# GPIO.net
KiCad netlist of a schematic drawn in Altium Designer
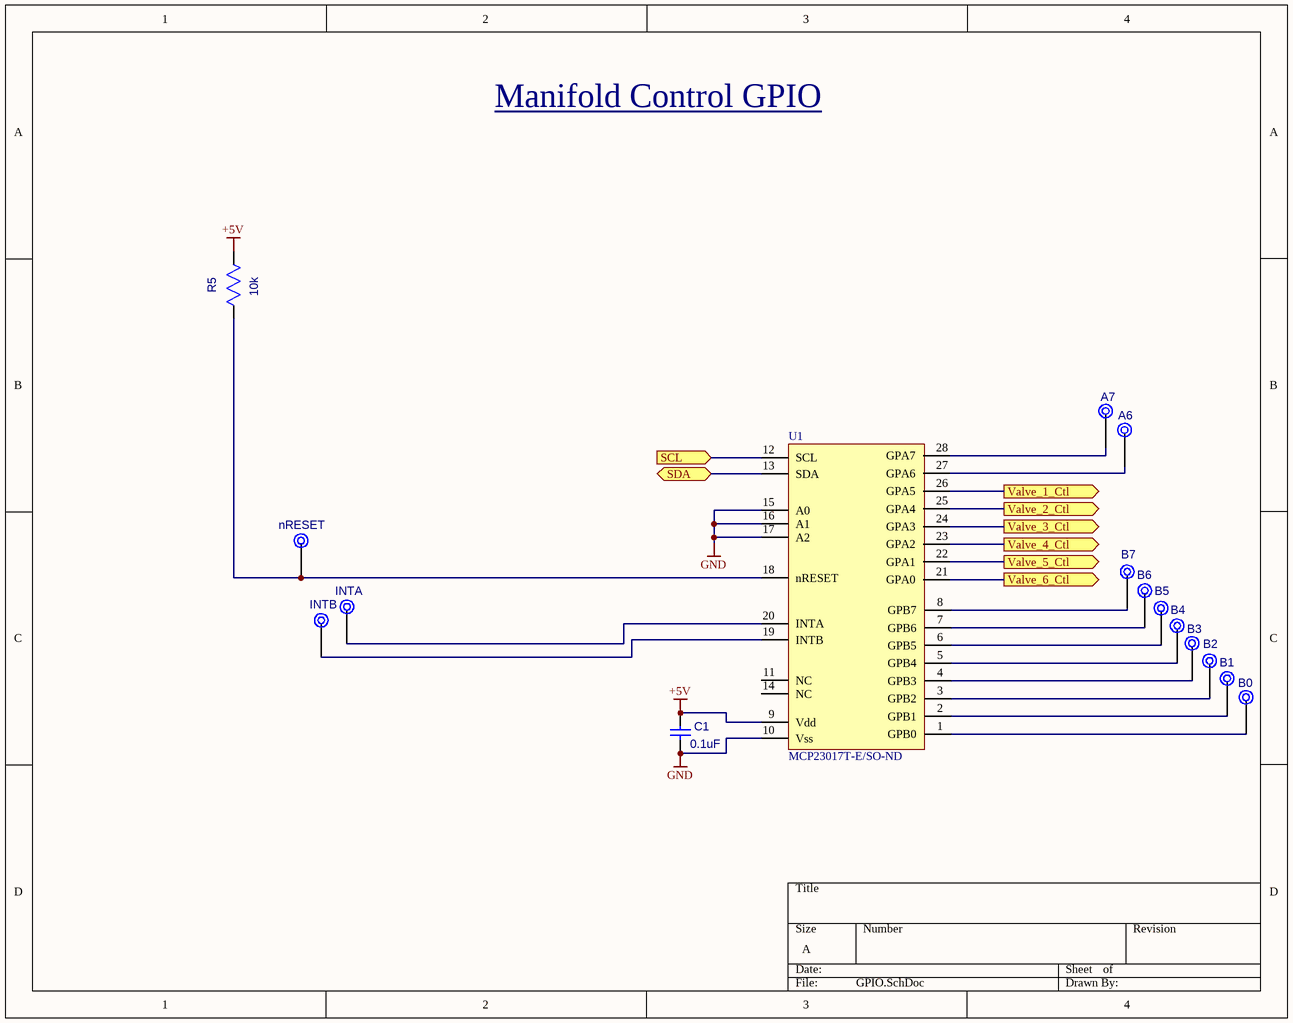
[diagram p0: GPIO.SchDoc]

(export (version "E")
  (design (tool "Eeschema 10.0.6"))
  (components
    (comp (ref "C1")
      (value "0.1uF")
      (footprint "CC1206")
      (description "CC1206")
      (libsource (lib "DBNOxVerI") (part "CC1206"))
    )
    (comp (ref "R5")
      (value "10k")
      (footprint "RC1206")
      (description "RC1206")
      (libsource (lib "DBNOxVerI") (part "RC1206"))
    )
    (comp (ref "TP1")
      (value "A6")
      (footprint "PAD_SMALL")
      (description "Test Point")
      (libsource (lib "DBNOxVerI") (part "PAD"))
    )
    (comp (ref "TP2")
      (value "A7")
      (footprint "PAD_SMALL")
      (description "Test Point")
      (libsource (lib "DBNOxVerI") (part "PAD"))
    )
    (comp (ref "TP3")
      (value "B0")
      (footprint "PAD_SMALL")
      (description "Test Point")
      (libsource (lib "DBNOxVerI") (part "PAD"))
    )
    (comp (ref "TP4")
      (value "B1")
      (footprint "PAD_SMALL")
      (description "Test Point")
      (libsource (lib "DBNOxVerI") (part "PAD"))
    )
    (comp (ref "TP5")
      (value "B2")
      (footprint "PAD_SMALL")
      (description "Test Point")
      (libsource (lib "DBNOxVerI") (part "PAD"))
    )
    (comp (ref "TP6")
      (value "B3")
      (footprint "PAD_SMALL")
      (description "Test Point")
      (libsource (lib "DBNOxVerI") (part "PAD"))
    )
    (comp (ref "TP7")
      (value "B4")
      (footprint "PAD_SMALL")
      (description "Test Point")
      (libsource (lib "DBNOxVerI") (part "PAD"))
    )
    (comp (ref "TP8")
      (value "B5")
      (footprint "PAD_SMALL")
      (description "Test Point")
      (libsource (lib "DBNOxVerI") (part "PAD"))
    )
    (comp (ref "TP9")
      (value "B6")
      (footprint "PAD_SMALL")
      (description "Test Point")
      (libsource (lib "DBNOxVerI") (part "PAD"))
    )
    (comp (ref "TP10")
      (value "B7")
      (footprint "PAD_SMALL")
      (description "Test Point")
      (libsource (lib "DBNOxVerI") (part "PAD"))
    )
    (comp (ref "TP11")
      (value "nRESET")
      (footprint "PAD_SMALL")
      (description "Test Point")
      (libsource (lib "DBNOxVerI") (part "PAD"))
    )
    (comp (ref "TP12")
      (value "INTA")
      (footprint "PAD_SMALL")
      (description "Test Point")
      (libsource (lib "DBNOxVerI") (part "PAD"))
    )
    (comp (ref "TP13")
      (value "INTB")
      (footprint "PAD_SMALL")
      (description "Test Point")
      (libsource (lib "DBNOxVerI") (part "PAD"))
    )
    (comp (ref "U1")
      (value "MCP23017-E/SO")
      (footprint "SOP28")
      (fields
        (field (name "MANUFACTURER") "Microchip Technology")
        (field (name "MANUFACTURER PART NUMBER") "MCP23017T-E/SO")
        (field (name "SUPPLIER PART NUMBER 1") "MCP23017T-E/SO-ND")
      )
      (libsource (lib "DBNOxVerI") (part "MCP23017-E/SO"))
    )
  )
  (nets
    (net (code "1") (name "+5V") (class "Default")
      (node (ref "C1") (pin "1") (pintype "passive"))
      (node (ref "R5") (pin "1") (pinfunction "1_1") (pintype "passive"))
      (node (ref "U1") (pin "9") (pinfunction "Vdd_9") (pintype "passive"))
    )
    (net (code "2") (name "/SCL") (class "Default")
      (node (ref "U1") (pin "12") (pinfunction "SCL_12") (pintype "passive"))
    )
    (net (code "3") (name "/SDA") (class "Default")
      (node (ref "U1") (pin "13") (pinfunction "SDA_13") (pintype "passive"))
    )
    (net (code "4") (name "/Valve_1_Ctl") (class "Default")
      (node (ref "U1") (pin "26") (pinfunction "GPA5_26") (pintype "passive"))
    )
    (net (code "5") (name "/Valve_2_Ctl") (class "Default")
      (node (ref "U1") (pin "25") (pinfunction "GPA4_25") (pintype "passive"))
    )
    (net (code "6") (name "/Valve_3_Ctl") (class "Default")
      (node (ref "U1") (pin "24") (pinfunction "GPA3_24") (pintype "passive"))
    )
    (net (code "7") (name "/Valve_4_Ctl") (class "Default")
      (node (ref "U1") (pin "23") (pinfunction "GPA2_23") (pintype "passive"))
    )
    (net (code "8") (name "/Valve_5_Ctl") (class "Default")
      (node (ref "U1") (pin "22") (pinfunction "GPA1_22") (pintype "passive"))
    )
    (net (code "9") (name "/Valve_6_Ctl") (class "Default")
      (node (ref "U1") (pin "21") (pinfunction "GPA0_21") (pintype "passive"))
    )
    (net (code "10") (name "GND") (class "Default")
      (node (ref "C1") (pin "2") (pintype "passive"))
      (node (ref "U1") (pin "10") (pinfunction "Vss_10") (pintype "passive"))
      (node (ref "U1") (pin "15") (pinfunction "A0_15") (pintype "passive"))
      (node (ref "U1") (pin "16") (pinfunction "A1_16") (pintype "passive"))
      (node (ref "U1") (pin "17") (pinfunction "A2_17") (pintype "passive"))
    )
    (net (code "11") (name "Net-(U1-GPA6)") (class "Default")
      (node (ref "TP1") (pin "TP") (pintype "passive"))
      (node (ref "U1") (pin "27") (pinfunction "GPA6_27") (pintype "passive"))
    )
    (net (code "12") (name "Net-(U1-GPA7)") (class "Default")
      (node (ref "TP2") (pin "TP") (pintype "passive"))
      (node (ref "U1") (pin "28") (pinfunction "GPA7_28") (pintype "passive"))
    )
    (net (code "13") (name "Net-(U1-GPB0)") (class "Default")
      (node (ref "TP3") (pin "TP") (pintype "passive"))
      (node (ref "U1") (pin "1") (pinfunction "GPB0_1") (pintype "passive"))
    )
    (net (code "14") (name "Net-(U1-GPB1)") (class "Default")
      (node (ref "TP4") (pin "TP") (pintype "passive"))
      (node (ref "U1") (pin "2") (pinfunction "GPB1_2") (pintype "passive"))
    )
    (net (code "15") (name "Net-(U1-GPB2)") (class "Default")
      (node (ref "TP5") (pin "TP") (pintype "passive"))
      (node (ref "U1") (pin "3") (pinfunction "GPB2_3") (pintype "passive"))
    )
    (net (code "16") (name "Net-(U1-GPB3)") (class "Default")
      (node (ref "TP6") (pin "TP") (pintype "passive"))
      (node (ref "U1") (pin "4") (pinfunction "GPB3_4") (pintype "passive"))
    )
    (net (code "17") (name "Net-(U1-GPB4)") (class "Default")
      (node (ref "TP7") (pin "TP") (pintype "passive"))
      (node (ref "U1") (pin "5") (pinfunction "GPB4_5") (pintype "passive"))
    )
    (net (code "18") (name "Net-(U1-GPB5)") (class "Default")
      (node (ref "TP8") (pin "TP") (pintype "passive"))
      (node (ref "U1") (pin "6") (pinfunction "GPB5_6") (pintype "passive"))
    )
    (net (code "19") (name "Net-(U1-GPB6)") (class "Default")
      (node (ref "TP9") (pin "TP") (pintype "passive"))
      (node (ref "U1") (pin "7") (pinfunction "GPB6_7") (pintype "passive"))
    )
    (net (code "20") (name "Net-(U1-GPB7)") (class "Default")
      (node (ref "TP10") (pin "TP") (pintype "passive"))
      (node (ref "U1") (pin "8") (pinfunction "GPB7_8") (pintype "passive"))
    )
    (net (code "21") (name "Net-(U1-INTA)") (class "Default")
      (node (ref "TP12") (pin "TP") (pintype "passive"))
      (node (ref "U1") (pin "20") (pinfunction "INTA_20") (pintype "passive"))
    )
    (net (code "22") (name "Net-(U1-INTB)") (class "Default")
      (node (ref "TP13") (pin "TP") (pintype "passive"))
      (node (ref "U1") (pin "19") (pinfunction "INTB_19") (pintype "passive"))
    )
    (net (code "23") (name "Net-(U1-nRESET)") (class "Default")
      (node (ref "R5") (pin "2") (pinfunction "2_2") (pintype "passive"))
      (node (ref "TP11") (pin "TP") (pintype "passive"))
      (node (ref "U1") (pin "18") (pinfunction "nRESET_18") (pintype "passive"))
    )
    (net (code "24") (name "unconnected-(U1-NC-Pad11)") (class "Default")
      (node (ref "U1") (pin "11") (pinfunction "NC_11") (pintype "passive"))
    )
    (net (code "25") (name "unconnected-(U1-NC-Pad14)") (class "Default")
      (node (ref "U1") (pin "14") (pinfunction "NC_14") (pintype "passive"))
    )
  )
)
